# PCB_Telemetria_2020.net
KiCad netlist of a schematic drawn in EAGLE
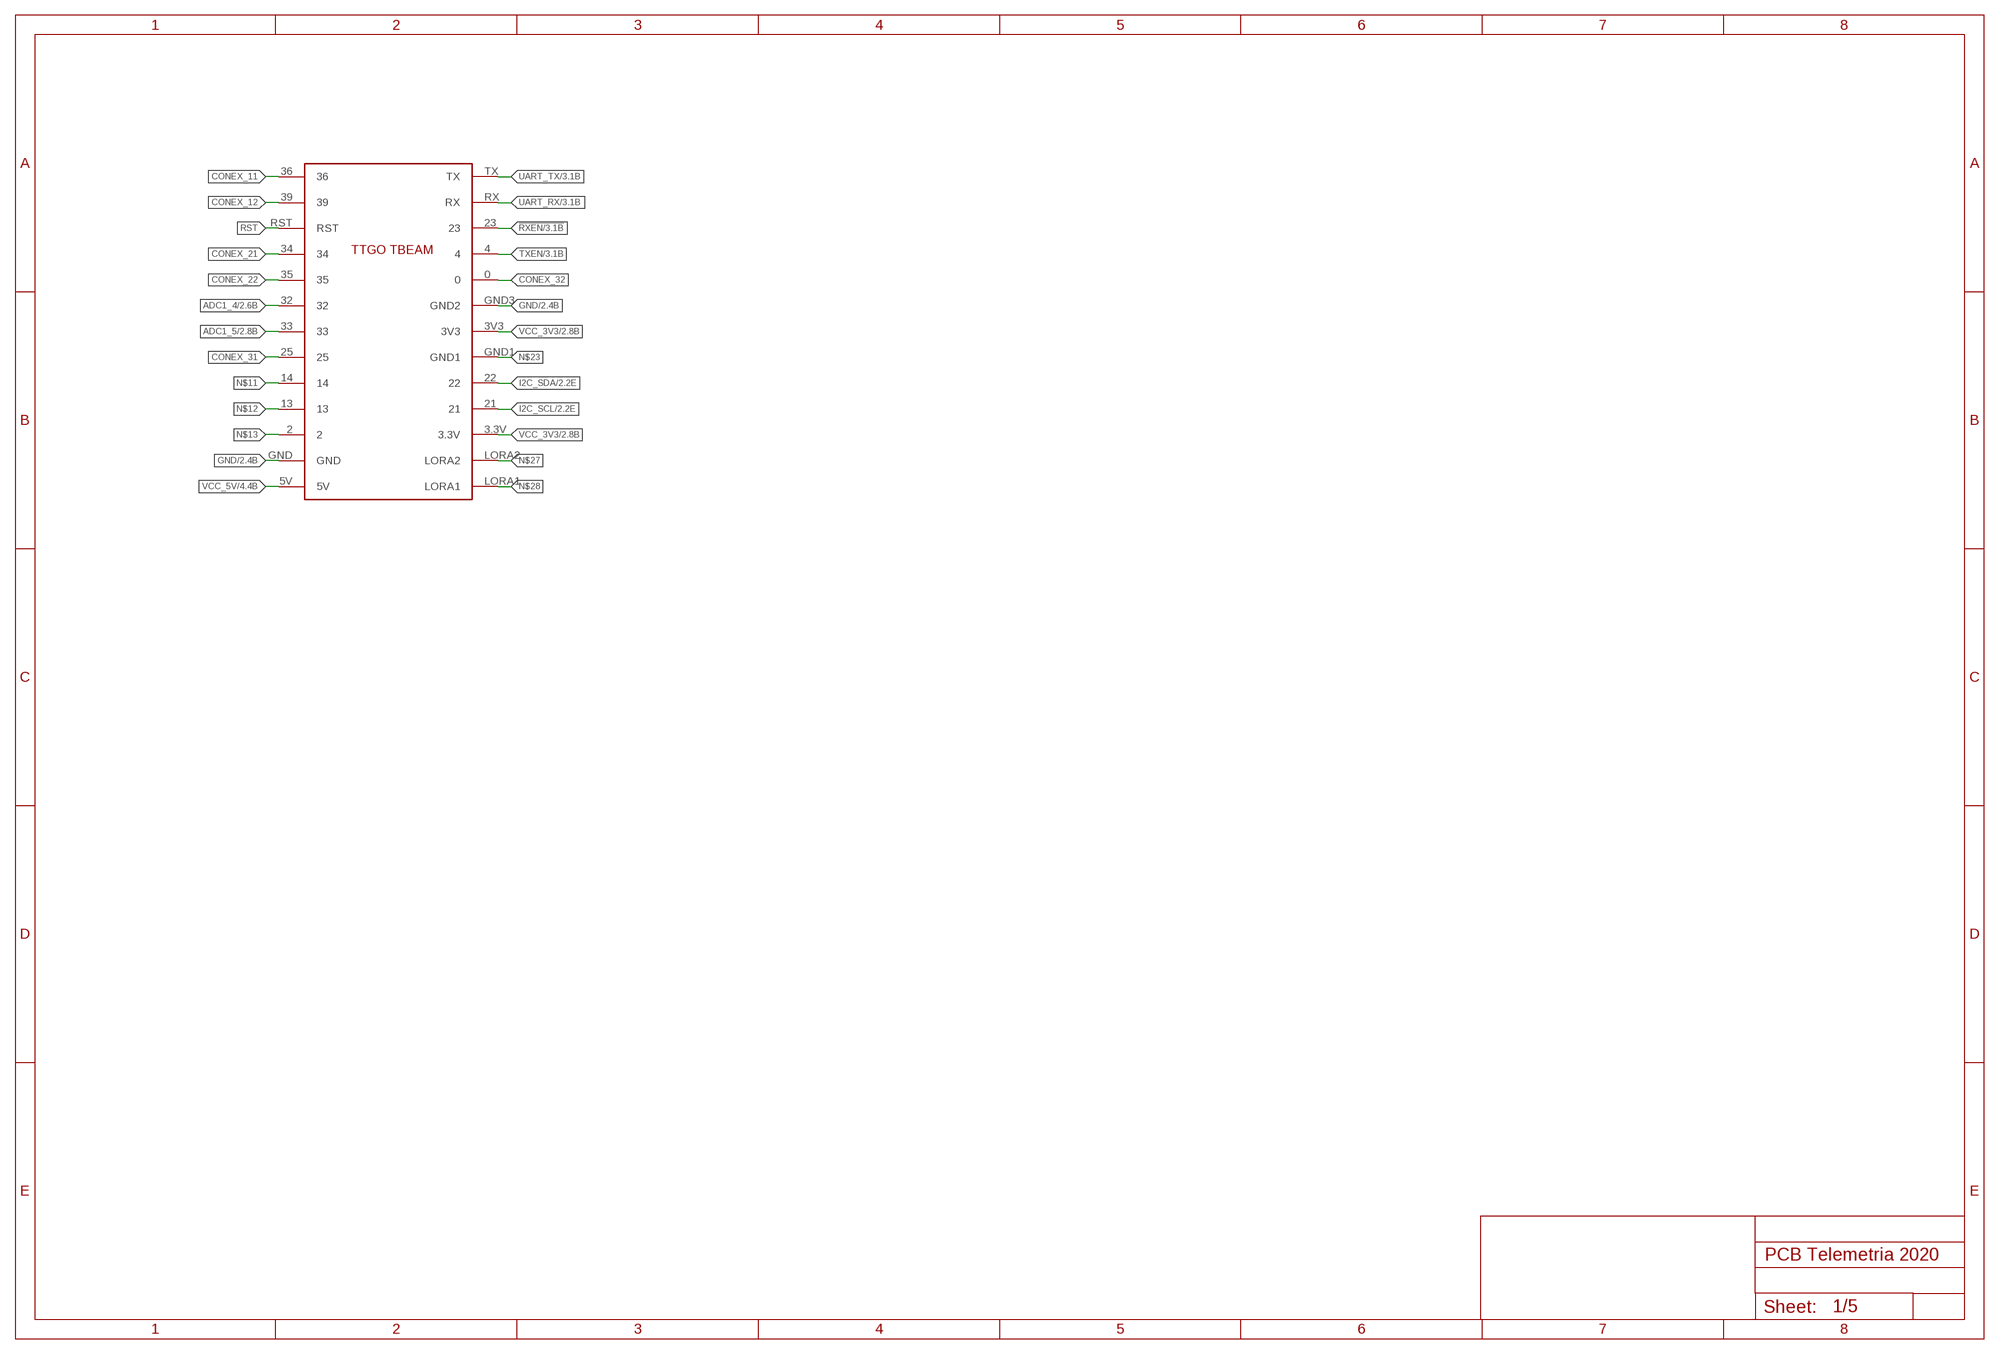
[diagram p0: schematic, sheet 1]
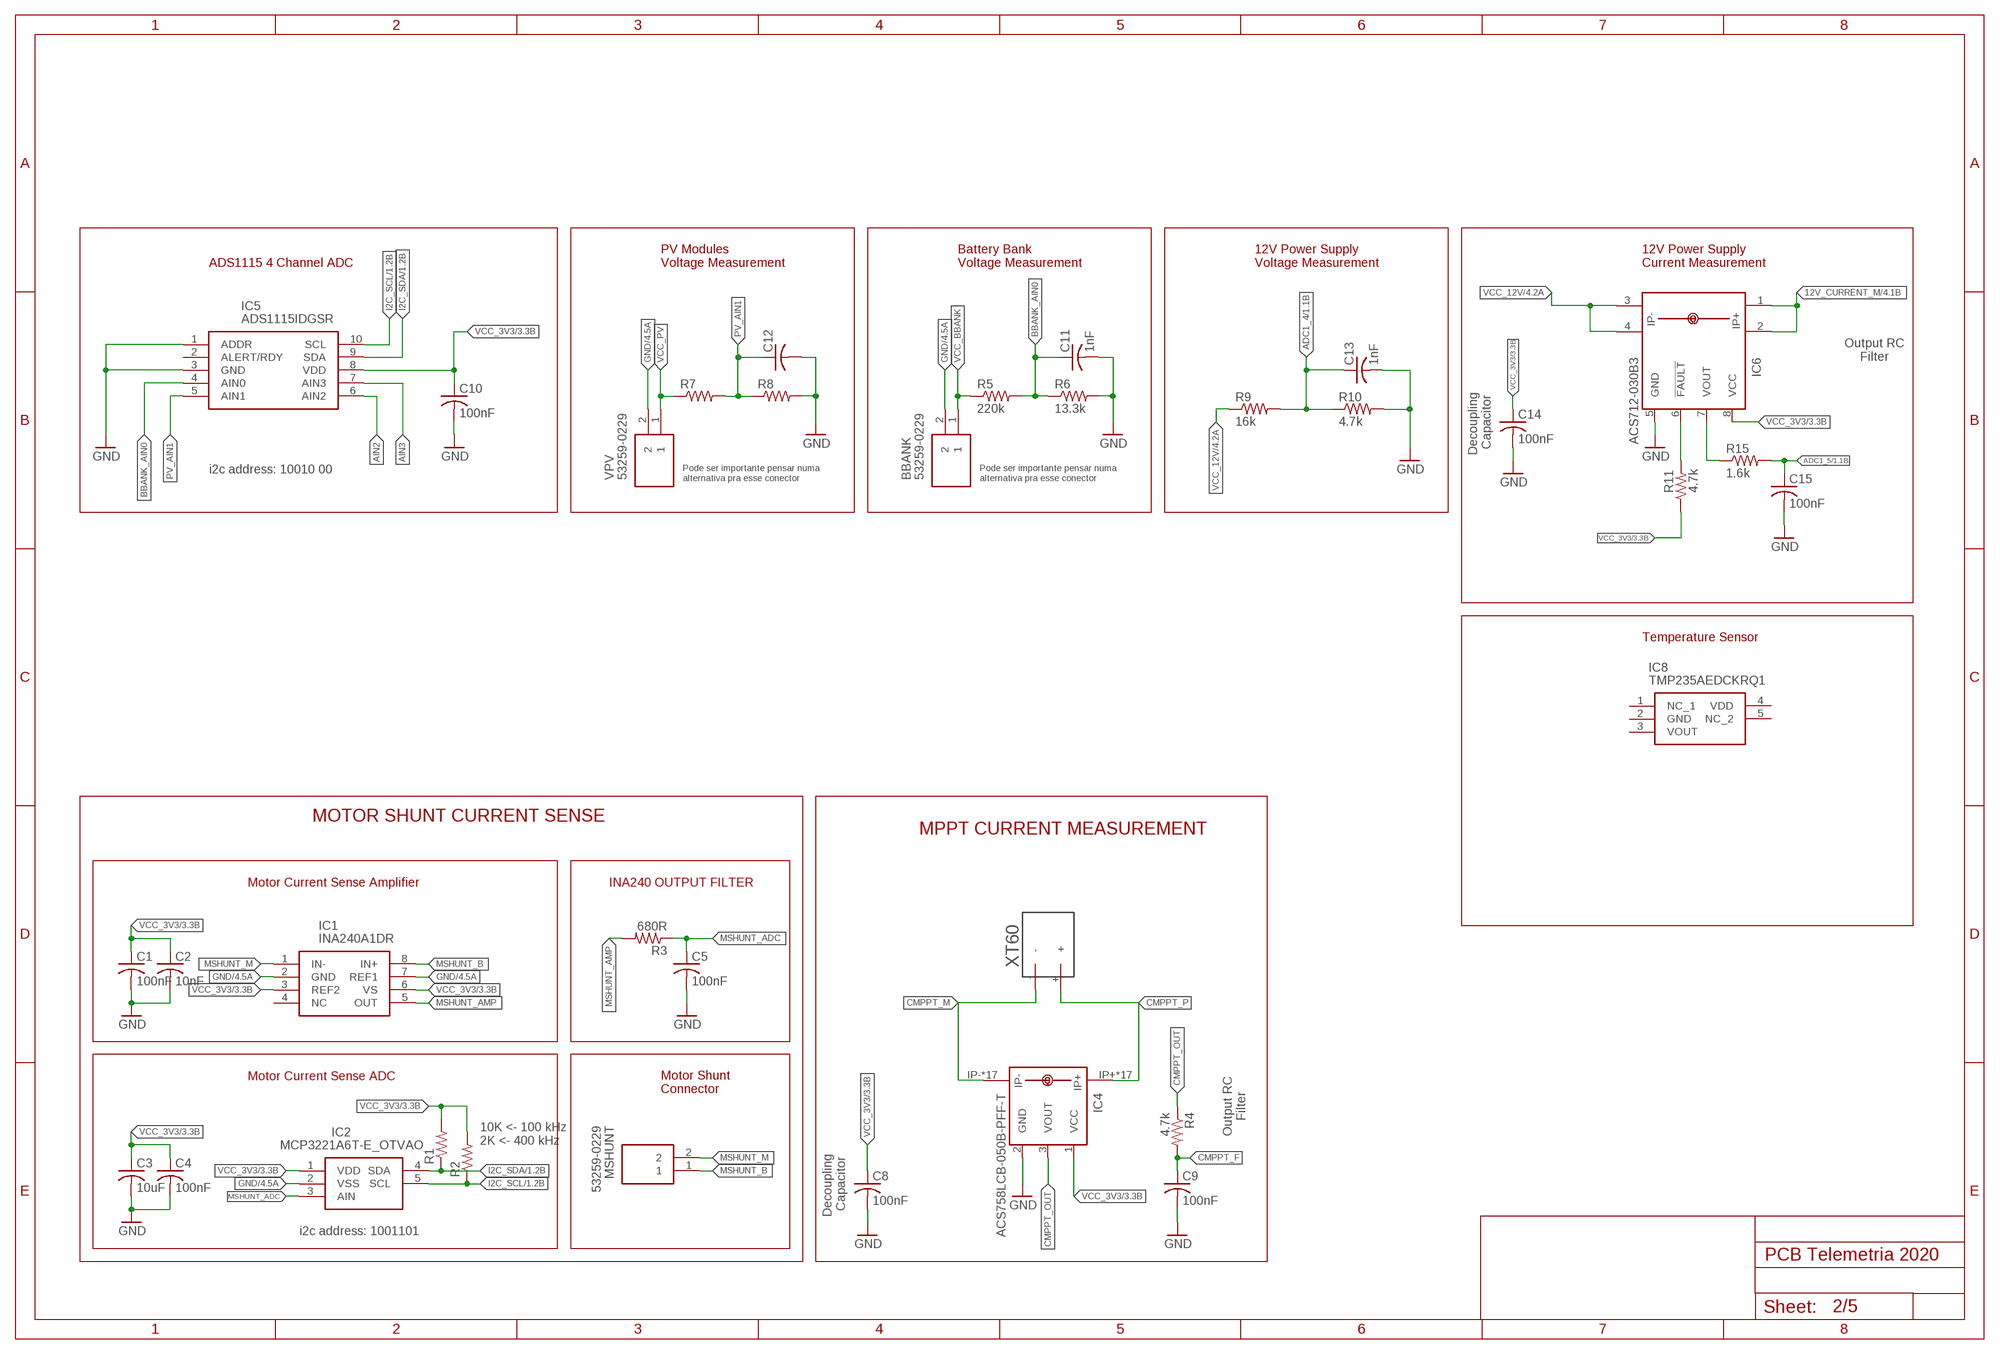
[diagram p1: schematic, sheet 2]
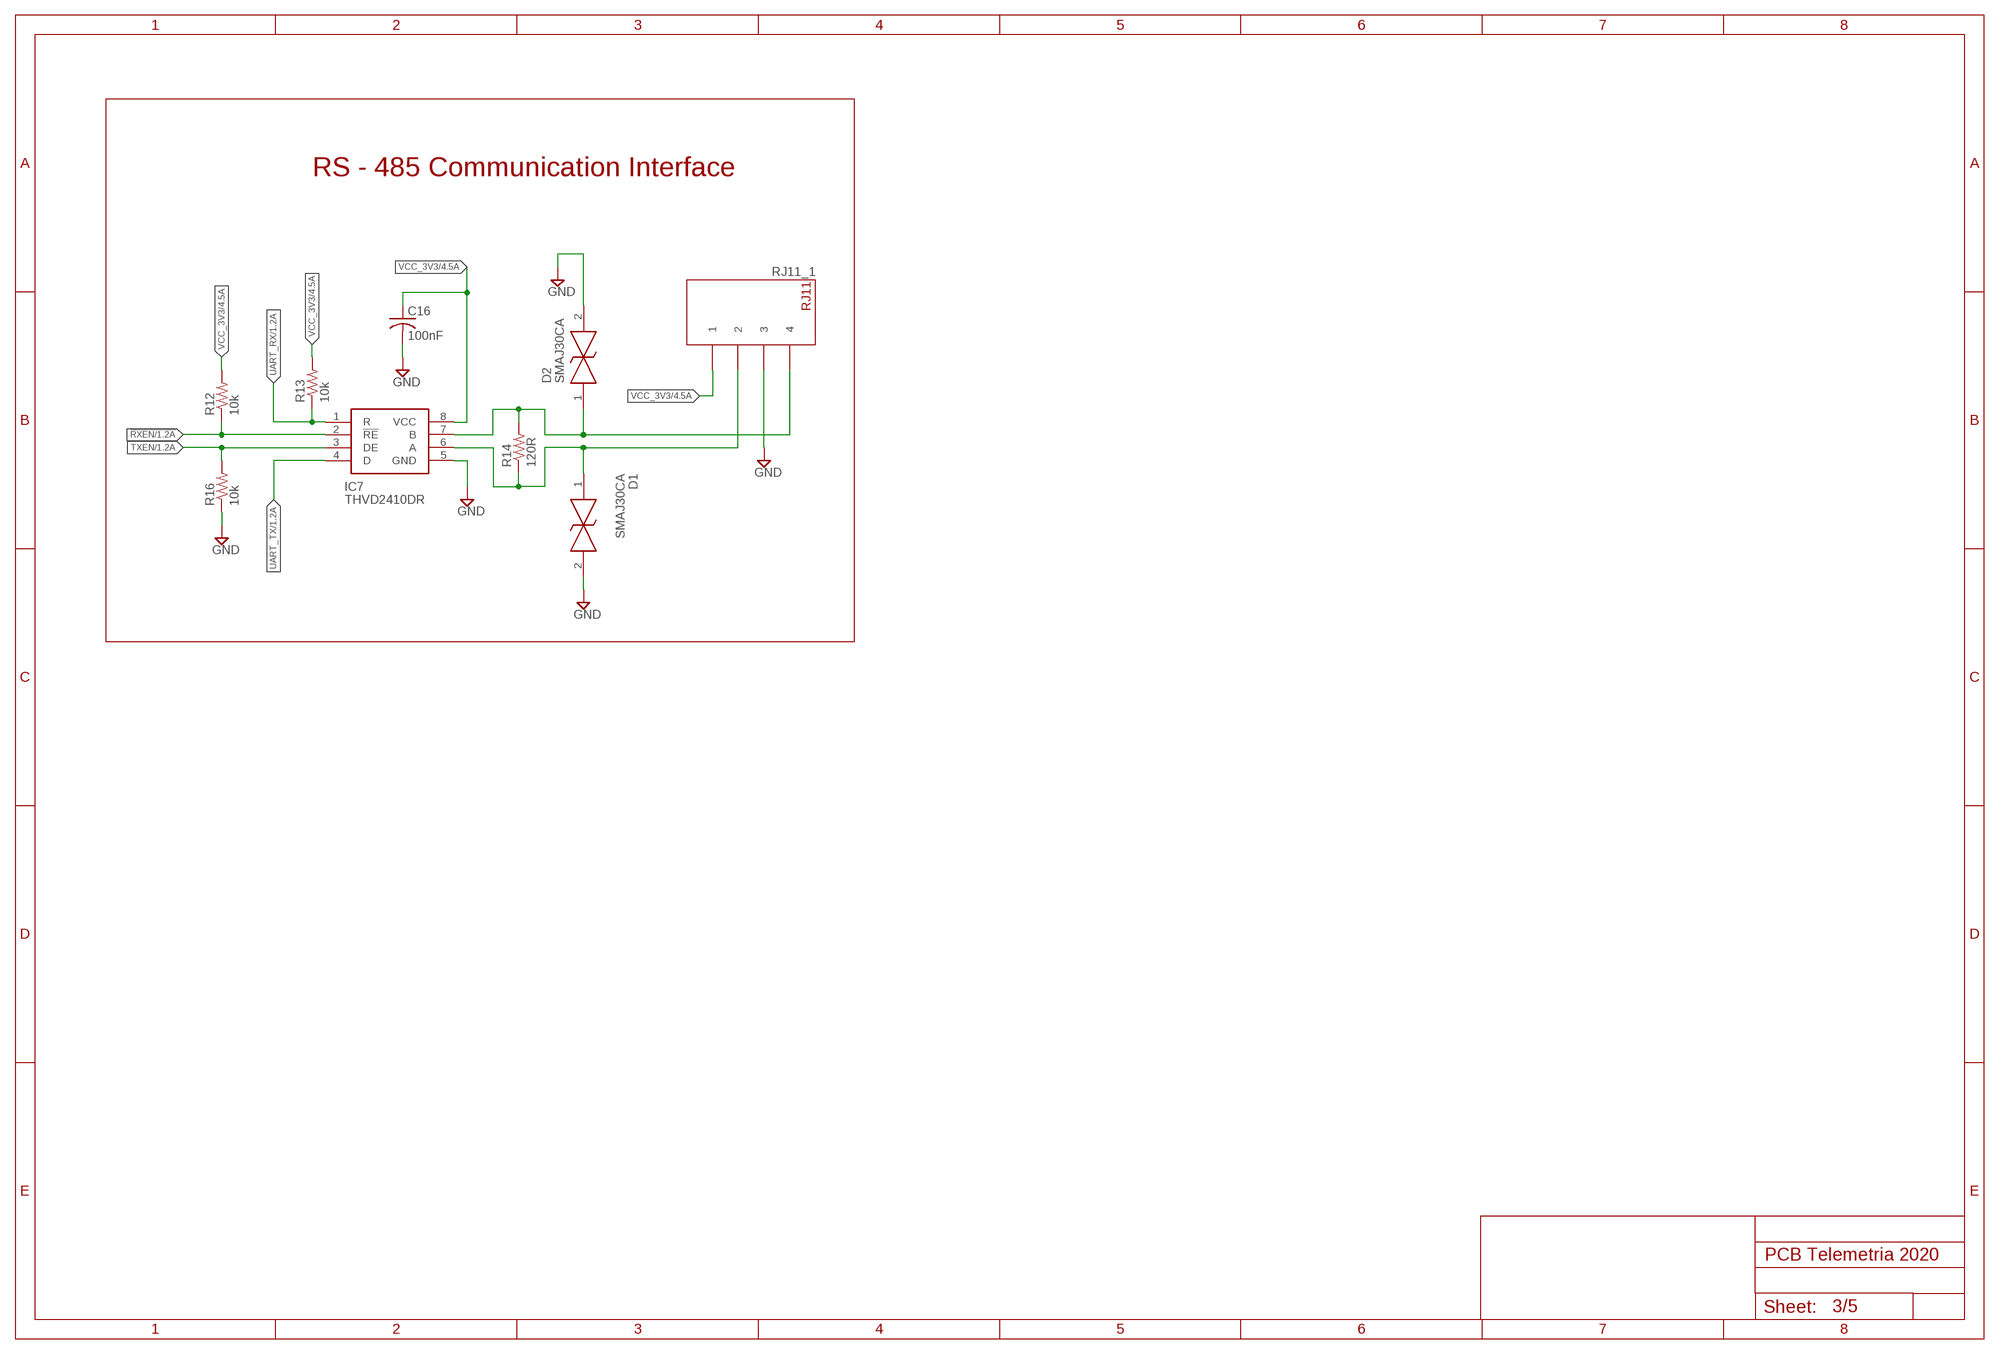
[diagram p2: schematic, sheet 3]
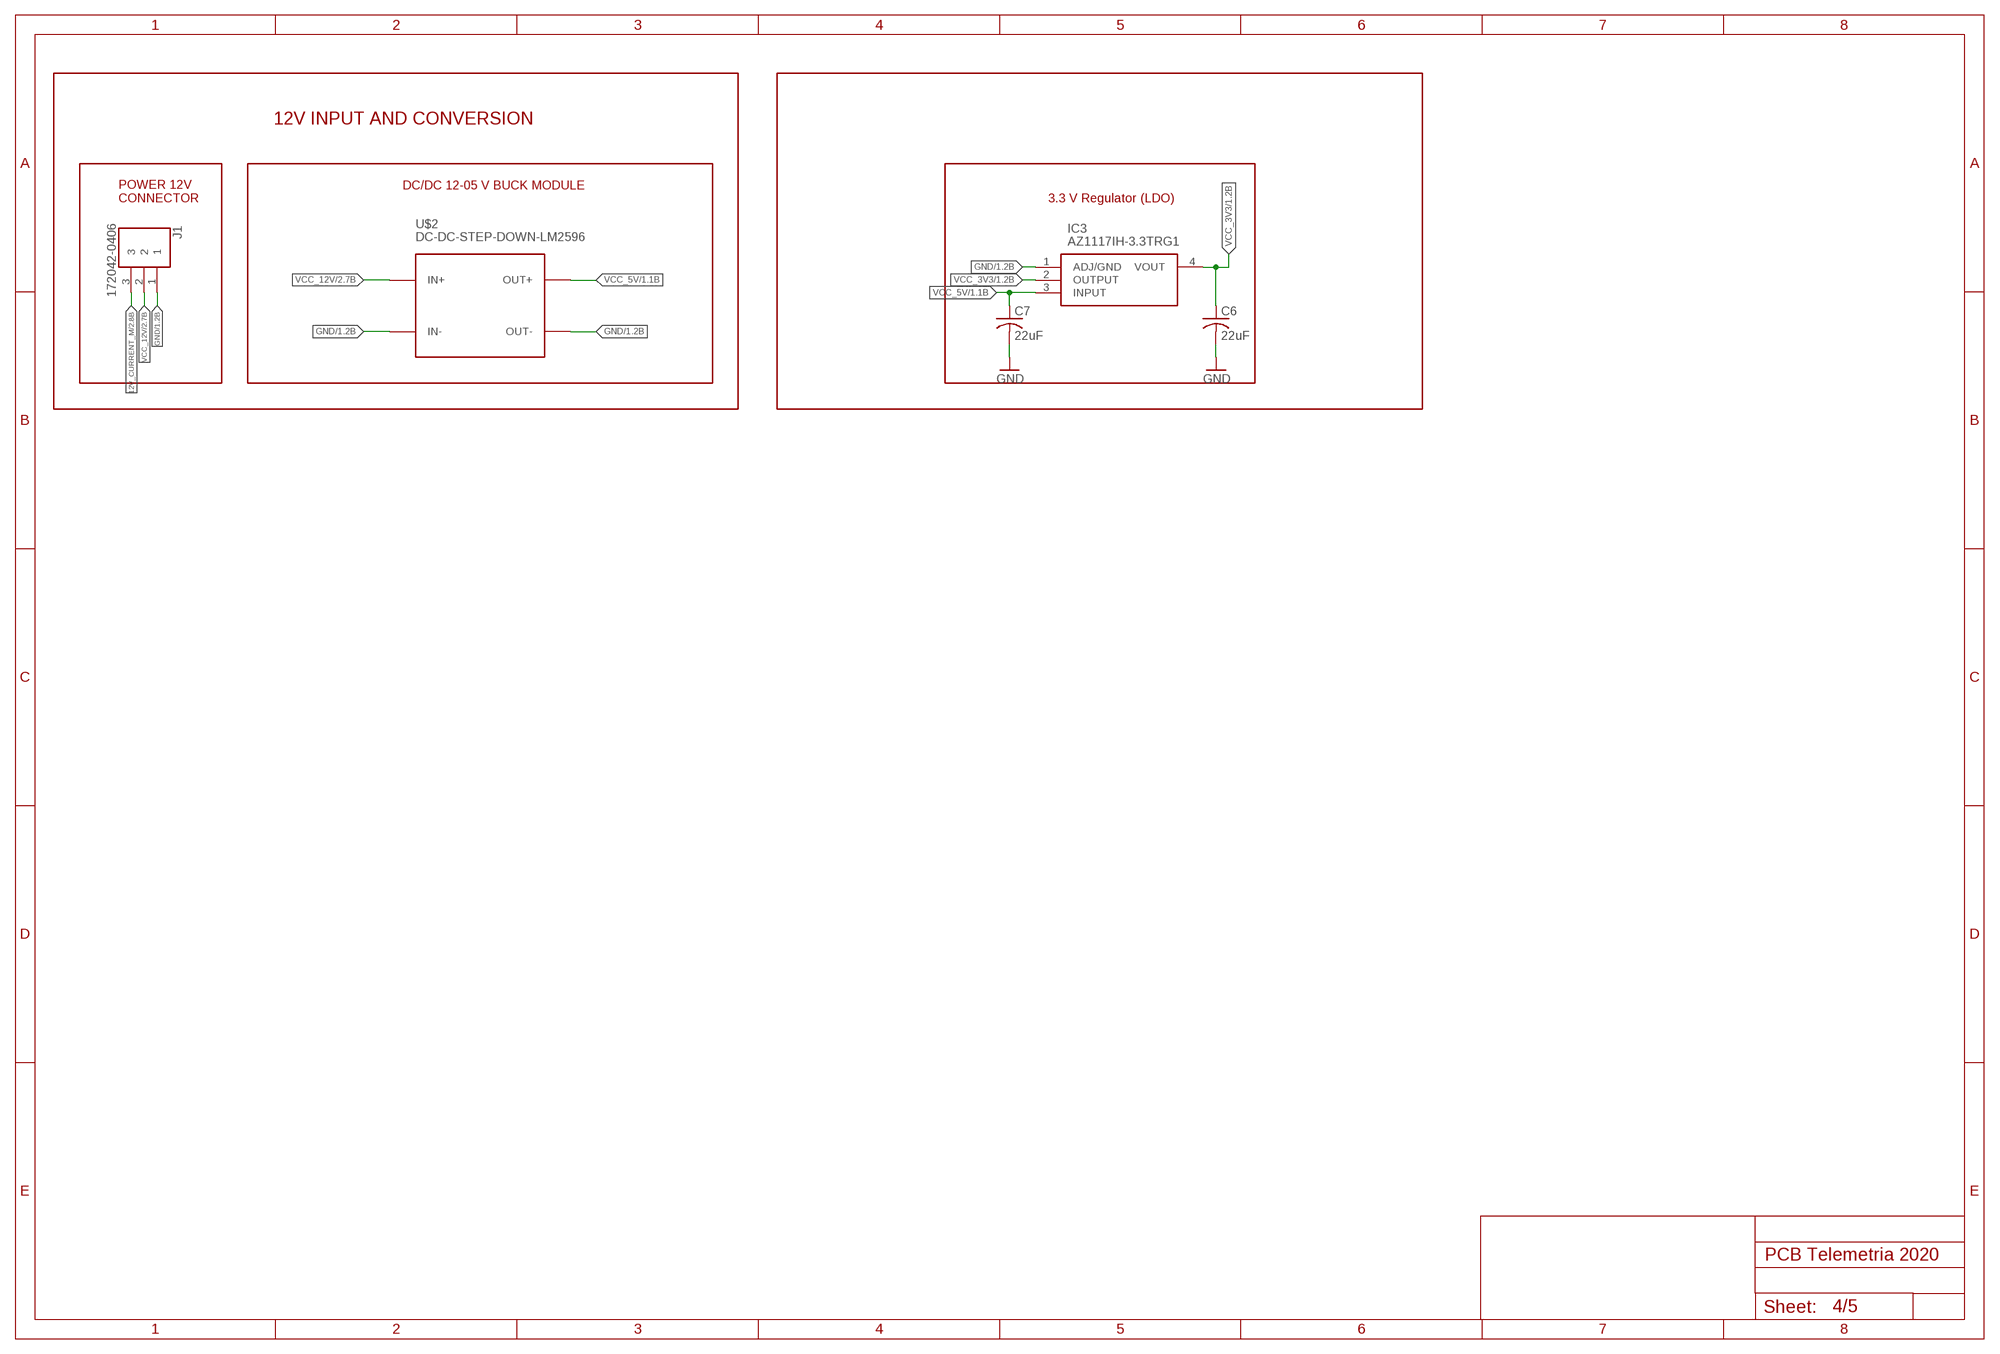
[diagram p3: schematic, sheet 4]
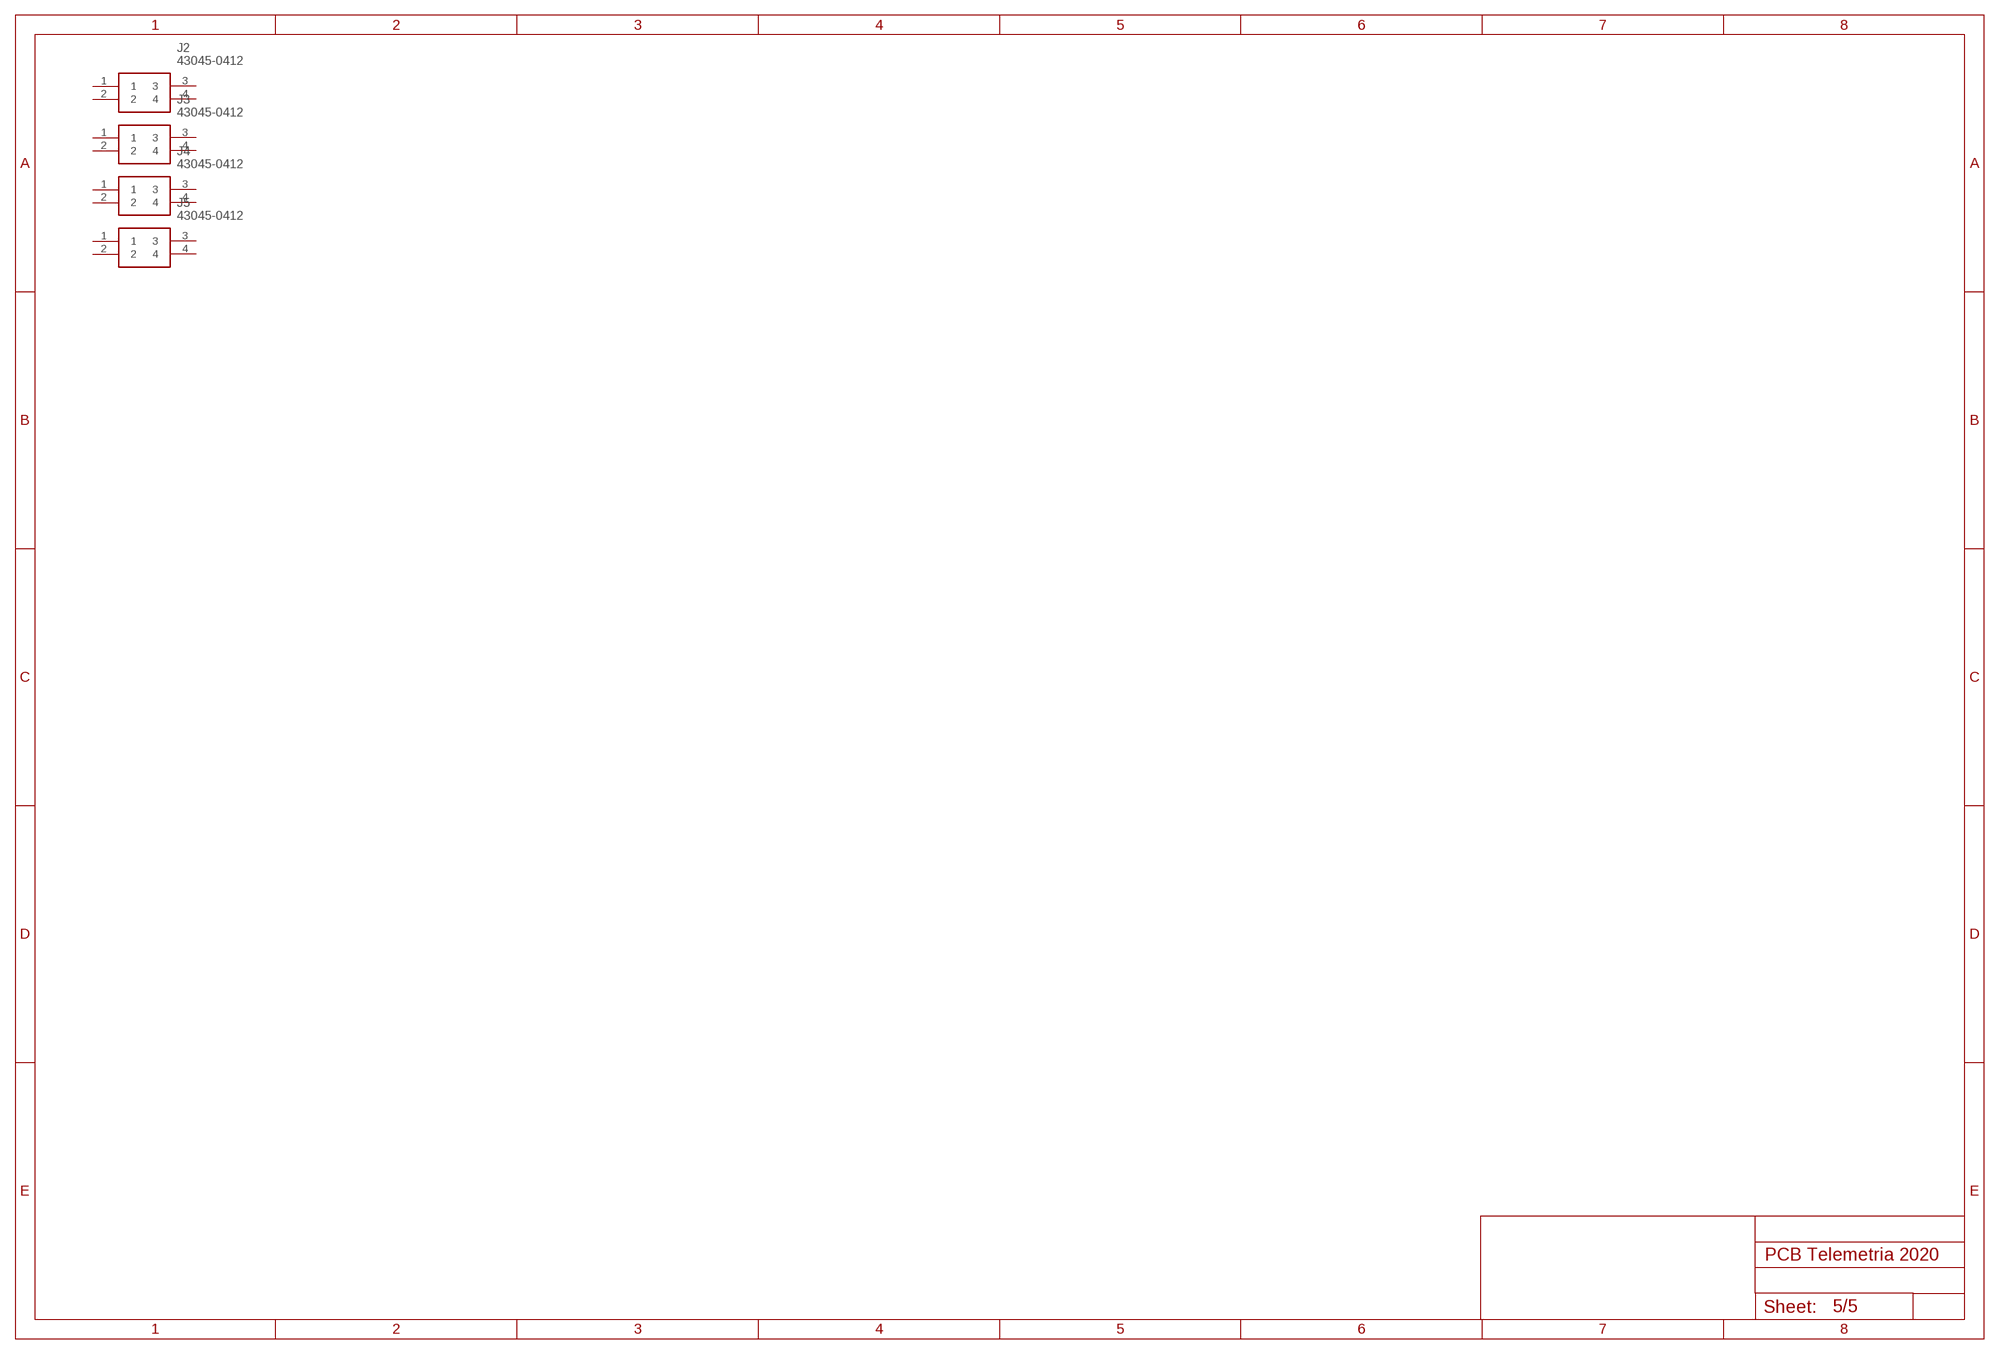
[diagram p4: schematic, sheet 5]

(export (version "E")
  (design (tool "Eeschema 10.0.6"))
  (components
    (comp (ref "U$1")
      (value "TTGOBEAM")
      (footprint "eagle-import:TTGOBEAM")
      (libsource (lib "eagle-import") (part "TTGOBEAM"))
    )
    (comp (ref "J2")
      (value "43045-0412")
      (footprint "eagle-import:43045-0412")
      (fields (field (name "MOUSER_PART_NUMBER") "538-43045-0412"))
      (libsource (lib "eagle-import") (part "43045-0412"))
    )
    (comp (ref "J3")
      (value "43045-0412")
      (footprint "eagle-import:43045-0412")
      (fields (field (name "MOUSER_PART_NUMBER") "538-43045-0412"))
      (libsource (lib "eagle-import") (part "43045-0412"))
    )
    (comp (ref "J4")
      (value "43045-0412")
      (footprint "eagle-import:43045-0412")
      (fields (field (name "MOUSER_PART_NUMBER") "538-43045-0412"))
      (libsource (lib "eagle-import") (part "43045-0412"))
    )
    (comp (ref "J5")
      (value "43045-0412")
      (footprint "eagle-import:43045-0412")
      (fields (field (name "MOUSER_PART_NUMBER") "538-43045-0412"))
      (libsource (lib "eagle-import") (part "43045-0412"))
    )
    (comp (ref "C6")
      (value "22uF")
      (footprint "eagle-import:C0805")
      (libsource (lib "eagle-import") (part "C-USC0805"))
    )
    (comp (ref "C7")
      (value "22uF")
      (footprint "eagle-import:C0805")
      (libsource (lib "eagle-import") (part "C-USC0805"))
    )
    (comp (ref "IC3")
      (value "AZ1117IH-3.3TRG1")
      (footprint "eagle-import:SOT230P700X170-4N")
      (fields (field (name "MOUSER_PART_NUMBER") "621-AZ1117IH-3.3TRG1"))
      (libsource (lib "eagle-import") (part "AZ1117IH-3.3TRG1"))
    )
    (comp (ref "J1")
      (value "172042-0406")
      (footprint "eagle-import:MOLEX_172042-0406")
      (fields (field (name "MF") "Molex") (field (name "MP") "172042-0302"))
      (libsource (lib "eagle-import") (part "172042-0406"))
    )
    (comp (ref "U$2")
      (value "DC-DC-STEP-DOWN-LM2596")
      (footprint "eagle-import:DC-DC-STEP-DOWN-LM2596")
      (libsource (lib "eagle-import") (part "DC-DC-STEP-DOWN-LM2596"))
    )
    (comp (ref "BBANK")
      (value "53259-0229")
      (footprint "eagle-import:0532590229")
      (fields (field (name "MOUSER_PART_NUMBER") "538-53259-0229"))
      (libsource (lib "eagle-import") (part "53259-0229"))
    )
    (comp (ref "C1")
      (value "100nF")
      (footprint "eagle-import:C0805")
      (libsource (lib "eagle-import") (part "C-USC0805"))
    )
    (comp (ref "C2")
      (value "10nF")
      (footprint "eagle-import:C0805")
      (libsource (lib "eagle-import") (part "C-USC0805"))
    )
    (comp (ref "C3")
      (value "10uF")
      (footprint "eagle-import:C0805")
      (libsource (lib "eagle-import") (part "C-USC0805"))
    )
    (comp (ref "C4")
      (value "100nF")
      (footprint "eagle-import:C0805")
      (libsource (lib "eagle-import") (part "C-USC0805"))
    )
    (comp (ref "C5")
      (value "100nF")
      (footprint "eagle-import:C0805")
      (libsource (lib "eagle-import") (part "C-USC0805"))
    )
    (comp (ref "C8")
      (value "100nF")
      (footprint "eagle-import:C0805")
      (libsource (lib "eagle-import") (part "C-USC0805"))
    )
    (comp (ref "C9")
      (value "100nF")
      (footprint "eagle-import:C0805")
      (libsource (lib "eagle-import") (part "C-USC0805"))
    )
    (comp (ref "C10")
      (value "100nF")
      (footprint "eagle-import:C0805")
      (libsource (lib "eagle-import") (part "C-USC0805"))
    )
    (comp (ref "C11")
      (value "1nF")
      (footprint "eagle-import:C0805")
      (libsource (lib "eagle-import") (part "C-USC0805"))
    )
    (comp (ref "C12")
      (value "C-USC0805")
      (footprint "eagle-import:C0805")
      (libsource (lib "eagle-import") (part "C-USC0805"))
    )
    (comp (ref "C13")
      (value "1nF")
      (footprint "eagle-import:C0805")
      (libsource (lib "eagle-import") (part "C-USC0805"))
    )
    (comp (ref "C14")
      (value "100nF")
      (footprint "eagle-import:C0805")
      (libsource (lib "eagle-import") (part "C-USC0805"))
    )
    (comp (ref "C15")
      (value "100nF")
      (footprint "eagle-import:C0805")
      (libsource (lib "eagle-import") (part "C-USC0805"))
    )
    (comp (ref "IC1")
      (value "INA240A1DR")
      (footprint "eagle-import:SOIC127P600X175-8N")
      (fields (field (name "MOUSER_PART_NUMBER") "595-INA240A1DR"))
      (libsource (lib "eagle-import") (part "INA240A1DR"))
    )
    (comp (ref "IC2")
      (value "MCP3221A6T-E_OTVAO")
      (footprint "eagle-import:SOT95P280X145-5N")
      (fields
        (field (name "MANUFACTURER_PART_NUMBER") "MCP3221A6T-E/OTVAO")
        (field (name "MOUSER_PART_NUMBER") "579-MCP3221A6TEOTVAO")
      )
      (libsource (lib "eagle-import") (part "MCP3221A6T-E_OTVAO"))
    )
    (comp (ref "IC4")
      (value "ACS758LCB-050B-PFF-T")
      (footprint "eagle-import:CB-PFF")
      (libsource (lib "eagle-import") (part "ACS758LCB-050B-PFF-T"))
    )
    (comp (ref "IC5")
      (value "ADS1115IDGSR")
      (footprint "eagle-import:SOP50P490X110-10N")
      (fields (field (name "MOUSER_PART_NUMBER") "595-ADS1115IDGSR"))
      (libsource (lib "eagle-import") (part "ADS1115IDGSR"))
    )
    (comp (ref "IC6")
      (value "ACS712-030B3")
      (footprint "eagle-import:SOIC8")
      (libsource (lib "eagle-import") (part "ACS712-LC"))
    )
    (comp (ref "IC8")
      (value "TMP235AEDCKRQ1")
      (footprint "eagle-import:SOT65P210X110-5N")
      (fields (field (name "MOUSER_PART_NUMBER") "595-TMP235AEDCKRQ1"))
      (libsource (lib "eagle-import") (part "TMP235AEDCKRQ1"))
    )
    (comp (ref "MSHUNT")
      (value "53259-0229")
      (footprint "eagle-import:0532590229")
      (fields (field (name "MOUSER_PART_NUMBER") "538-53259-0229"))
      (libsource (lib "eagle-import") (part "53259-0229"))
    )
    (comp (ref "R1")
      (value "R-US_R0805")
      (footprint "eagle-import:R0805")
      (libsource (lib "eagle-import") (part "R-US_R0805"))
    )
    (comp (ref "R2")
      (value "R-US_R0805")
      (footprint "eagle-import:R0805")
      (libsource (lib "eagle-import") (part "R-US_R0805"))
    )
    (comp (ref "R3")
      (value "680R")
      (footprint "eagle-import:R0805")
      (libsource (lib "eagle-import") (part "R-US_R0805"))
    )
    (comp (ref "R4")
      (value "4.7k")
      (footprint "eagle-import:R0805")
      (libsource (lib "eagle-import") (part "R-US_R0805"))
    )
    (comp (ref "R5")
      (value "220k")
      (footprint "eagle-import:R0805")
      (libsource (lib "eagle-import") (part "R-US_R0805"))
    )
    (comp (ref "R6")
      (value "13.3k")
      (footprint "eagle-import:R0805")
      (libsource (lib "eagle-import") (part "R-US_R0805"))
    )
    (comp (ref "R7")
      (value "R-US_R0805")
      (footprint "eagle-import:R0805")
      (libsource (lib "eagle-import") (part "R-US_R0805"))
    )
    (comp (ref "R8")
      (value "R-US_R0805")
      (footprint "eagle-import:R0805")
      (libsource (lib "eagle-import") (part "R-US_R0805"))
    )
    (comp (ref "R9")
      (value "16k")
      (footprint "eagle-import:R0805")
      (libsource (lib "eagle-import") (part "R-US_R0805"))
    )
    (comp (ref "R10")
      (value "4.7k")
      (footprint "eagle-import:R0805")
      (libsource (lib "eagle-import") (part "R-US_R0805"))
    )
    (comp (ref "R11")
      (value "4.7k")
      (footprint "eagle-import:R0805")
      (libsource (lib "eagle-import") (part "R-US_R0805"))
    )
    (comp (ref "R15")
      (value "1.6k")
      (footprint "eagle-import:R0805")
      (libsource (lib "eagle-import") (part "R-US_R0805"))
    )
    (comp (ref "U$3")
      (value "XT60")
      (footprint "eagle-import:XT60")
      (libsource (lib "eagle-import") (part "XT60"))
    )
    (comp (ref "VPV")
      (value "53259-0229")
      (footprint "eagle-import:0532590229")
      (fields (field (name "MOUSER_PART_NUMBER") "538-53259-0229"))
      (libsource (lib "eagle-import") (part "53259-0229"))
    )
    (comp (ref "C16")
      (value "100nF")
      (footprint "eagle-import:C0805")
      (libsource (lib "eagle-import") (part "C-USC0805"))
    )
    (comp (ref "D1")
      (value "SMAJ30CA")
      (footprint "eagle-import:DIONM5026X229N")
      (fields (field (name "MOUSER_PART_NUMBER") "576-SMAJ30CA"))
      (libsource (lib "eagle-import") (part "SMAJ30CA"))
    )
    (comp (ref "D2")
      (value "SMAJ30CA")
      (footprint "eagle-import:DIONM5026X229N")
      (fields (field (name "MOUSER_PART_NUMBER") "576-SMAJ30CA"))
      (libsource (lib "eagle-import") (part "SMAJ30CA"))
    )
    (comp (ref "IC7")
      (value "THVD2410DR")
      (footprint "eagle-import:SOIC127P600X175-8N")
      (fields (field (name "MOUSER_PART_NUMBER") "595-THVD2410DR"))
      (libsource (lib "eagle-import") (part "THVD2410DR"))
    )
    (comp (ref "R12")
      (value "10k")
      (footprint "eagle-import:M0805")
      (libsource (lib "eagle-import") (part "R-US_M0805"))
    )
    (comp (ref "R13")
      (value "10k")
      (footprint "eagle-import:M0805")
      (libsource (lib "eagle-import") (part "R-US_M0805"))
    )
    (comp (ref "R14")
      (value "120R")
      (footprint "eagle-import:M0805")
      (libsource (lib "eagle-import") (part "R-US_M0805"))
    )
    (comp (ref "R16")
      (value "10k")
      (footprint "eagle-import:M0805")
      (libsource (lib "eagle-import") (part "R-US_M0805"))
    )
    (comp (ref "RJ11_1")
      (value "TFC44")
      (footprint "eagle-import:TFC44")
      (libsource (lib "eagle-import") (part "TFC44"))
    )
  )
  (nets
    (net (code "1") (name "12V_CURRENT_M") (class "Default")
      (node (ref "IC6") (pin "1") (pinfunction "IP+_1") (pintype "passive"))
      (node (ref "IC6") (pin "2") (pinfunction "IP+1_2") (pintype "passive"))
      (node (ref "J1") (pin "3") (pinfunction "3_3") (pintype "passive"))
    )
    (net (code "2") (name "ADC1_4") (class "Default")
      (node (ref "C13") (pin "1") (pinfunction "1_1") (pintype "passive"))
      (node (ref "R10") (pin "1") (pinfunction "1_1") (pintype "passive"))
      (node (ref "R9") (pin "2") (pinfunction "2_2") (pintype "passive"))
      (node (ref "U$1") (pin "32") (pinfunction "32_32") (pintype "bidirectional"))
    )
    (net (code "3") (name "ADC1_5") (class "Default")
      (node (ref "C15") (pin "1") (pinfunction "1_1") (pintype "passive"))
      (node (ref "R15") (pin "2") (pinfunction "2_2") (pintype "passive"))
      (node (ref "U$1") (pin "33") (pinfunction "33_33") (pintype "bidirectional"))
    )
    (net (code "4") (name "AIN2") (class "Default")
      (node (ref "IC5") (pin "6") (pinfunction "AIN2_6") (pintype "bidirectional"))
    )
    (net (code "5") (name "AIN3") (class "Default")
      (node (ref "IC5") (pin "7") (pinfunction "AIN3_7") (pintype "bidirectional"))
    )
    (net (code "6") (name "BBANK_AIN0") (class "Default")
      (node (ref "C11") (pin "1") (pinfunction "1_1") (pintype "passive"))
      (node (ref "IC5") (pin "4") (pinfunction "AIN0_4") (pintype "bidirectional"))
      (node (ref "R5") (pin "2") (pinfunction "2_2") (pintype "passive"))
      (node (ref "R6") (pin "1") (pinfunction "1_1") (pintype "passive"))
    )
    (net (code "7") (name "CMPPT_F") (class "Default")
      (node (ref "C9") (pin "1") (pinfunction "1_1") (pintype "passive"))
      (node (ref "R4") (pin "2") (pinfunction "2_2") (pintype "passive"))
    )
    (net (code "8") (name "CMPPT_M") (class "Default")
      (node (ref "IC4") (pin "IP-") (pinfunction "IP-_IP-") (pintype "passive"))
      (node (ref "IC4") (pin "IP-@10") (pinfunction "IP-_IP-@10") (pintype "passive"))
      (node (ref "IC4") (pin "IP-@11") (pinfunction "IP-_IP-@11") (pintype "passive"))
      (node (ref "IC4") (pin "IP-@12") (pinfunction "IP-_IP-@12") (pintype "passive"))
      (node (ref "IC4") (pin "IP-@13") (pinfunction "IP-_IP-@13") (pintype "passive"))
      (node (ref "IC4") (pin "IP-@14") (pinfunction "IP-_IP-@14") (pintype "passive"))
      (node (ref "IC4") (pin "IP-@15") (pinfunction "IP-_IP-@15") (pintype "passive"))
      (node (ref "IC4") (pin "IP-@16") (pinfunction "IP-_IP-@16") (pintype "passive"))
      (node (ref "IC4") (pin "IP-@17") (pinfunction "IP-_IP-@17") (pintype "passive"))
      (node (ref "IC4") (pin "IP-@2") (pinfunction "IP-_IP-@2") (pintype "passive"))
      (node (ref "IC4") (pin "IP-@3") (pinfunction "IP-_IP-@3") (pintype "passive"))
      (node (ref "IC4") (pin "IP-@4") (pinfunction "IP-_IP-@4") (pintype "passive"))
      (node (ref "IC4") (pin "IP-@5") (pinfunction "IP-_IP-@5") (pintype "passive"))
      (node (ref "IC4") (pin "IP-@6") (pinfunction "IP-_IP-@6") (pintype "passive"))
      (node (ref "IC4") (pin "IP-@7") (pinfunction "IP-_IP-@7") (pintype "passive"))
      (node (ref "IC4") (pin "IP-@8") (pinfunction "IP-_IP-@8") (pintype "passive"))
      (node (ref "IC4") (pin "IP-@9") (pinfunction "IP-_IP-@9") (pintype "passive"))
      (node (ref "U$3") (pin "-") (pinfunction "-_-") (pintype "bidirectional"))
    )
    (net (code "9") (name "CMPPT_OUT") (class "Default")
      (node (ref "IC4") (pin "3") (pinfunction "VOUT_3") (pintype "output"))
      (node (ref "R4") (pin "1") (pinfunction "1_1") (pintype "passive"))
    )
    (net (code "10") (name "CMPPT_P") (class "Default")
      (node (ref "IC4") (pin "IP+") (pinfunction "IP+_IP+") (pintype "passive"))
      (node (ref "IC4") (pin "IP+@10") (pinfunction "IP+_IP+@10") (pintype "passive"))
      (node (ref "IC4") (pin "IP+@11") (pinfunction "IP+_IP+@11") (pintype "passive"))
      (node (ref "IC4") (pin "IP+@12") (pinfunction "IP+_IP+@12") (pintype "passive"))
      (node (ref "IC4") (pin "IP+@13") (pinfunction "IP+_IP+@13") (pintype "passive"))
      (node (ref "IC4") (pin "IP+@14") (pinfunction "IP+_IP+@14") (pintype "passive"))
      (node (ref "IC4") (pin "IP+@15") (pinfunction "IP+_IP+@15") (pintype "passive"))
      (node (ref "IC4") (pin "IP+@16") (pinfunction "IP+_IP+@16") (pintype "passive"))
      (node (ref "IC4") (pin "IP+@17") (pinfunction "IP+_IP+@17") (pintype "passive"))
      (node (ref "IC4") (pin "IP+@2") (pinfunction "IP+_IP+@2") (pintype "passive"))
      (node (ref "IC4") (pin "IP+@3") (pinfunction "IP+_IP+@3") (pintype "passive"))
      (node (ref "IC4") (pin "IP+@4") (pinfunction "IP+_IP+@4") (pintype "passive"))
      (node (ref "IC4") (pin "IP+@5") (pinfunction "IP+_IP+@5") (pintype "passive"))
      (node (ref "IC4") (pin "IP+@6") (pinfunction "IP+_IP+@6") (pintype "passive"))
      (node (ref "IC4") (pin "IP+@7") (pinfunction "IP+_IP+@7") (pintype "passive"))
      (node (ref "IC4") (pin "IP+@8") (pinfunction "IP+_IP+@8") (pintype "passive"))
      (node (ref "IC4") (pin "IP+@9") (pinfunction "IP+_IP+@9") (pintype "passive"))
      (node (ref "U$3") (pin "+") (pinfunction "+_+") (pintype "bidirectional"))
    )
    (net (code "11") (name "CONEX_11") (class "Default")
      (node (ref "U$1") (pin "36") (pinfunction "36_36") (pintype "bidirectional"))
    )
    (net (code "12") (name "CONEX_12") (class "Default")
      (node (ref "U$1") (pin "39") (pinfunction "39_39") (pintype "bidirectional"))
    )
    (net (code "13") (name "CONEX_21") (class "Default")
      (node (ref "U$1") (pin "34") (pinfunction "34_34") (pintype "bidirectional"))
    )
    (net (code "14") (name "CONEX_22") (class "Default")
      (node (ref "U$1") (pin "35") (pinfunction "35_35") (pintype "bidirectional"))
    )
    (net (code "15") (name "CONEX_31") (class "Default")
      (node (ref "U$1") (pin "25") (pinfunction "25_25") (pintype "bidirectional"))
    )
    (net (code "16") (name "CONEX_32") (class "Default")
      (node (ref "U$1") (pin "0") (pinfunction "0_0") (pintype "bidirectional"))
    )
    (net (code "17") (name "GND") (class "Default")
      (node (ref "BBANK") (pin "2") (pinfunction "2_2") (pintype "bidirectional"))
      (node (ref "C1") (pin "2") (pinfunction "2_2") (pintype "passive"))
      (node (ref "C10") (pin "2") (pinfunction "2_2") (pintype "passive"))
      (node (ref "C11") (pin "2") (pinfunction "2_2") (pintype "passive"))
      (node (ref "C12") (pin "2") (pinfunction "2_2") (pintype "passive"))
      (node (ref "C13") (pin "2") (pinfunction "2_2") (pintype "passive"))
      (node (ref "C14") (pin "2") (pinfunction "2_2") (pintype "passive"))
      (node (ref "C15") (pin "2") (pinfunction "2_2") (pintype "passive"))
      (node (ref "C16") (pin "2") (pinfunction "2_2") (pintype "passive"))
      (node (ref "C2") (pin "2") (pinfunction "2_2") (pintype "passive"))
      (node (ref "C3") (pin "2") (pinfunction "2_2") (pintype "passive"))
      (node (ref "C4") (pin "2") (pinfunction "2_2") (pintype "passive"))
      (node (ref "C5") (pin "2") (pinfunction "2_2") (pintype "passive"))
      (node (ref "C6") (pin "2") (pinfunction "2_2") (pintype "passive"))
      (node (ref "C7") (pin "2") (pinfunction "2_2") (pintype "passive"))
      (node (ref "C8") (pin "2") (pinfunction "2_2") (pintype "passive"))
      (node (ref "C9") (pin "2") (pinfunction "2_2") (pintype "passive"))
      (node (ref "D1") (pin "2") (pinfunction "2_2") (pintype "bidirectional"))
      (node (ref "D2") (pin "2") (pinfunction "2_2") (pintype "bidirectional"))
      (node (ref "IC1") (pin "2") (pinfunction "GND_2") (pintype "bidirectional"))
      (node (ref "IC1") (pin "7") (pinfunction "REF1_7") (pintype "bidirectional"))
      (node (ref "IC2") (pin "2") (pinfunction "VSS_2") (pintype "bidirectional"))
      (node (ref "IC3") (pin "1") (pinfunction "ADJ/GND_1") (pintype "bidirectional"))
      (node (ref "IC4") (pin "2") (pinfunction "GND_2") (pintype "power_in"))
      (node (ref "IC5") (pin "1") (pinfunction "ADDR_1") (pintype "bidirectional"))
      (node (ref "IC5") (pin "3") (pinfunction "GND_3") (pintype "bidirectional"))
      (node (ref "IC6") (pin "5") (pinfunction "GND_5") (pintype "power_in"))
      (node (ref "IC7") (pin "5") (pinfunction "GND_5") (pintype "bidirectional"))
      (node (ref "J1") (pin "1") (pinfunction "1_1") (pintype "passive"))
      (node (ref "R10") (pin "2") (pinfunction "2_2") (pintype "passive"))
      (node (ref "R16") (pin "1") (pinfunction "1_1") (pintype "passive"))
      (node (ref "R6") (pin "2") (pinfunction "2_2") (pintype "passive"))
      (node (ref "R8") (pin "2") (pinfunction "2_2") (pintype "passive"))
      (node (ref "RJ11_1") (pin "P$3") (pinfunction "3_P$3") (pintype "bidirectional"))
      (node (ref "U$1") (pin "GND") (pinfunction "GND_GND") (pintype "bidirectional"))
      (node (ref "U$1") (pin "GND3") (pinfunction "GND2_GND3") (pintype "bidirectional"))
      (node (ref "U$2") (pin "IN-") (pinfunction "IN-_IN-") (pintype "bidirectional"))
      (node (ref "U$2") (pin "OUT-") (pinfunction "OUT-_OUT-") (pintype "bidirectional"))
      (node (ref "VPV") (pin "2") (pinfunction "2_2") (pintype "bidirectional"))
    )
    (net (code "18") (name "I2C_SCL") (class "Default")
      (node (ref "IC2") (pin "5") (pinfunction "SCL_5") (pintype "bidirectional"))
      (node (ref "IC5") (pin "10") (pinfunction "SCL_10") (pintype "bidirectional"))
      (node (ref "R2") (pin "1") (pinfunction "1_1") (pintype "passive"))
      (node (ref "U$1") (pin "21") (pinfunction "21_21") (pintype "bidirectional"))
    )
    (net (code "19") (name "I2C_SDA") (class "Default")
      (node (ref "IC2") (pin "4") (pinfunction "SDA_4") (pintype "bidirectional"))
      (node (ref "IC5") (pin "9") (pinfunction "SDA_9") (pintype "bidirectional"))
      (node (ref "R1") (pin "1") (pinfunction "1_1") (pintype "passive"))
      (node (ref "U$1") (pin "22") (pinfunction "22_22") (pintype "bidirectional"))
    )
    (net (code "20") (name "MSHUNT_ADC") (class "Default")
      (node (ref "C5") (pin "1") (pinfunction "1_1") (pintype "passive"))
      (node (ref "IC2") (pin "3") (pinfunction "AIN_3") (pintype "bidirectional"))
      (node (ref "R3") (pin "1") (pinfunction "1_1") (pintype "passive"))
    )
    (net (code "21") (name "MSHUNT_AMP") (class "Default")
      (node (ref "IC1") (pin "5") (pinfunction "OUT_5") (pintype "bidirectional"))
      (node (ref "R3") (pin "2") (pinfunction "2_2") (pintype "passive"))
    )
    (net (code "22") (name "MSHUNT_B") (class "Default")
      (node (ref "IC1") (pin "8") (pinfunction "IN+_8") (pintype "bidirectional"))
      (node (ref "MSHUNT") (pin "1") (pinfunction "1_1") (pintype "bidirectional"))
    )
    (net (code "23") (name "MSHUNT_M") (class "Default")
      (node (ref "IC1") (pin "1") (pinfunction "IN-_1") (pintype "bidirectional"))
      (node (ref "MSHUNT") (pin "2") (pinfunction "2_2") (pintype "bidirectional"))
    )
    (net (code "24") (name "N$11") (class "Default")
      (node (ref "U$1") (pin "14") (pinfunction "14_14") (pintype "bidirectional"))
    )
    (net (code "25") (name "N$12") (class "Default")
      (node (ref "U$1") (pin "13") (pinfunction "13_13") (pintype "bidirectional"))
    )
    (net (code "26") (name "N$13") (class "Default")
      (node (ref "U$1") (pin "2") (pinfunction "2_2") (pintype "bidirectional"))
    )
    (net (code "27") (name "N$23") (class "Default")
      (node (ref "U$1") (pin "GND1") (pinfunction "GND1_GND1") (pintype "bidirectional"))
    )
    (net (code "28") (name "N$27") (class "Default")
      (node (ref "U$1") (pin "LORA2") (pinfunction "LORA2_LORA2") (pintype "bidirectional"))
    )
    (net (code "29") (name "N$28") (class "Default")
      (node (ref "U$1") (pin "LORA1") (pinfunction "LORA1_LORA1") (pintype "bidirectional"))
    )
    (net (code "30") (name "Net-(IC6-VOUT)") (class "Default")
      (node (ref "IC6") (pin "7") (pinfunction "VOUT_7") (pintype "output"))
      (node (ref "R15") (pin "1") (pinfunction "1_1") (pintype "passive"))
    )
    (net (code "31") (name "Net-(IC6-~{FAULT})") (class "Default")
      (node (ref "IC6") (pin "6") (pinfunction "~{FAULT}_6") (pintype "bidirectional"))
      (node (ref "R11") (pin "2") (pinfunction "2_2") (pintype "passive"))
    )
    (net (code "32") (name "Net-(IC7-A)") (class "Default")
      (node (ref "D1") (pin "1") (pinfunction "1_1") (pintype "bidirectional"))
      (node (ref "IC7") (pin "6") (pinfunction "A_6") (pintype "bidirectional"))
      (node (ref "R14") (pin "1") (pinfunction "1_1") (pintype "passive"))
      (node (ref "RJ11_1") (pin "P$2") (pinfunction "2_P$2") (pintype "bidirectional"))
    )
    (net (code "33") (name "Net-(IC7-B)") (class "Default")
      (node (ref "D2") (pin "1") (pinfunction "1_1") (pintype "bidirectional"))
      (node (ref "IC7") (pin "7") (pinfunction "B_7") (pintype "bidirectional"))
      (node (ref "R14") (pin "2") (pinfunction "2_2") (pintype "passive"))
      (node (ref "RJ11_1") (pin "P$4") (pinfunction "4_P$4") (pintype "bidirectional"))
    )
    (net (code "34") (name "PV_AIN1") (class "Default")
      (node (ref "C12") (pin "1") (pinfunction "1_1") (pintype "passive"))
      (node (ref "IC5") (pin "5") (pinfunction "AIN1_5") (pintype "bidirectional"))
      (node (ref "R7") (pin "2") (pinfunction "2_2") (pintype "passive"))
      (node (ref "R8") (pin "1") (pinfunction "1_1") (pintype "passive"))
    )
    (net (code "35") (name "RST") (class "Default")
      (node (ref "U$1") (pin "RST") (pinfunction "RST_RST") (pintype "bidirectional"))
    )
    (net (code "36") (name "TXEN") (class "Default")
      (node (ref "IC7") (pin "3") (pinfunction "DE_3") (pintype "bidirectional"))
      (node (ref "R16") (pin "2") (pinfunction "2_2") (pintype "passive"))
      (node (ref "U$1") (pin "4") (pinfunction "4_4") (pintype "bidirectional"))
    )
    (net (code "37") (name "UART_RX") (class "Default")
      (node (ref "IC7") (pin "1") (pinfunction "R_1") (pintype "bidirectional"))
      (node (ref "R13") (pin "1") (pinfunction "1_1") (pintype "passive"))
      (node (ref "U$1") (pin "RX") (pinfunction "RX_RX") (pintype "bidirectional"))
    )
    (net (code "38") (name "UART_TX") (class "Default")
      (node (ref "IC7") (pin "4") (pinfunction "D_4") (pintype "bidirectional"))
      (node (ref "U$1") (pin "TX") (pinfunction "TX_TX") (pintype "bidirectional"))
    )
    (net (code "39") (name "VCC_3V3") (class "Default")
      (node (ref "C1") (pin "1") (pinfunction "1_1") (pintype "passive"))
      (node (ref "C10") (pin "1") (pinfunction "1_1") (pintype "passive"))
      (node (ref "C14") (pin "1") (pinfunction "1_1") (pintype "passive"))
      (node (ref "C16") (pin "1") (pinfunction "1_1") (pintype "passive"))
      (node (ref "C2") (pin "1") (pinfunction "1_1") (pintype "passive"))
      (node (ref "C3") (pin "1") (pinfunction "1_1") (pintype "passive"))
      (node (ref "C4") (pin "1") (pinfunction "1_1") (pintype "passive"))
      (node (ref "C6") (pin "1") (pinfunction "1_1") (pintype "passive"))
      (node (ref "C8") (pin "1") (pinfunction "1_1") (pintype "passive"))
      (node (ref "IC1") (pin "3") (pinfunction "REF2_3") (pintype "bidirectional"))
      (node (ref "IC1") (pin "6") (pinfunction "VS_6") (pintype "bidirectional"))
      (node (ref "IC2") (pin "1") (pinfunction "VDD_1") (pintype "bidirectional"))
      (node (ref "IC3") (pin "2") (pinfunction "OUTPUT_2") (pintype "bidirectional"))
      (node (ref "IC3") (pin "4") (pinfunction "VOUT_4") (pintype "bidirectional"))
      (node (ref "IC4") (pin "1") (pinfunction "VCC_1") (pintype "power_in"))
      (node (ref "IC5") (pin "8") (pinfunction "VDD_8") (pintype "bidirectional"))
      (node (ref "IC6") (pin "8") (pinfunction "VCC_8") (pintype "power_in"))
      (node (ref "IC7") (pin "8") (pinfunction "VCC_8") (pintype "bidirectional"))
      (node (ref "R1") (pin "2") (pinfunction "2_2") (pintype "passive"))
      (node (ref "R11") (pin "1") (pinfunction "1_1") (pintype "passive"))
      (node (ref "R12") (pin "2") (pinfunction "2_2") (pintype "passive"))
      (node (ref "R13") (pin "2") (pinfunction "2_2") (pintype "passive"))
      (node (ref "R2") (pin "2") (pinfunction "2_2") (pintype "passive"))
      (node (ref "RJ11_1") (pin "P$1") (pinfunction "1_P$1") (pintype "bidirectional"))
      (node (ref "U$1") (pin "3.3V") (pinfunction "3.3V_3.3V") (pintype "bidirectional"))
      (node (ref "U$1") (pin "3V3") (pinfunction "3V3_3V3") (pintype "bidirectional"))
    )
    (net (code "40") (name "VCC_5V") (class "Default")
      (node (ref "C7") (pin "1") (pinfunction "1_1") (pintype "passive"))
      (node (ref "IC3") (pin "3") (pinfunction "INPUT_3") (pintype "bidirectional"))
      (node (ref "U$1") (pin "5V") (pinfunction "5V_5V") (pintype "bidirectional"))
      (node (ref "U$2") (pin "OUT+") (pinfunction "OUT+_OUT+") (pintype "bidirectional"))
    )
    (net (code "41") (name "VCC_12V") (class "Default")
      (node (ref "IC6") (pin "3") (pinfunction "IP-_3") (pintype "passive"))
      (node (ref "IC6") (pin "4") (pinfunction "IP-1_4") (pintype "passive"))
      (node (ref "J1") (pin "2") (pinfunction "2_2") (pintype "passive"))
      (node (ref "R9") (pin "1") (pinfunction "1_1") (pintype "passive"))
      (node (ref "U$2") (pin "IN+") (pinfunction "IN+_IN+") (pintype "bidirectional"))
    )
    (net (code "42") (name "VCC_BBANK") (class "Default")
      (node (ref "BBANK") (pin "1") (pinfunction "1_1") (pintype "bidirectional"))
      (node (ref "R5") (pin "1") (pinfunction "1_1") (pintype "passive"))
    )
    (net (code "43") (name "VCC_PV") (class "Default")
      (node (ref "R7") (pin "1") (pinfunction "1_1") (pintype "passive"))
      (node (ref "VPV") (pin "1") (pinfunction "1_1") (pintype "bidirectional"))
    )
    (net (code "44") (name "unconnected-(IC1-NC-Pad4)") (class "Default")
      (node (ref "IC1") (pin "4") (pinfunction "NC_4") (pintype "no_connect"))
    )
    (net (code "45") (name "unconnected-(IC5-ALERT{slash}RDY-Pad2)") (class "Default")
      (node (ref "IC5") (pin "2") (pinfunction "ALERT/RDY_2") (pintype "bidirectional"))
    )
    (net (code "46") (name "unconnected-(IC8-GND-Pad2)") (class "Default")
      (node (ref "IC8") (pin "2") (pinfunction "GND_2") (pintype "bidirectional"))
    )
    (net (code "47") (name "unconnected-(IC8-NC_1-Pad1)") (class "Default")
      (node (ref "IC8") (pin "1") (pinfunction "NC_1_1") (pintype "bidirectional"))
    )
    (net (code "48") (name "unconnected-(IC8-NC_2-Pad5)") (class "Default")
      (node (ref "IC8") (pin "5") (pinfunction "NC_2_5") (pintype "bidirectional"))
    )
    (net (code "49") (name "unconnected-(IC8-VDD-Pad4)") (class "Default")
      (node (ref "IC8") (pin "4") (pinfunction "VDD_4") (pintype "bidirectional"))
    )
    (net (code "50") (name "unconnected-(IC8-VOUT-Pad3)") (class "Default")
      (node (ref "IC8") (pin "3") (pinfunction "VOUT_3") (pintype "bidirectional"))
    )
    (net (code "51") (name "unconnected-(J2-Pad1)") (class "Default")
      (node (ref "J2") (pin "1") (pinfunction "1_1") (pintype "bidirectional"))
    )
    (net (code "52") (name "unconnected-(J2-Pad2)") (class "Default")
      (node (ref "J2") (pin "2") (pinfunction "2_2") (pintype "bidirectional"))
    )
    (net (code "53") (name "unconnected-(J2-Pad3)") (class "Default")
      (node (ref "J2") (pin "3") (pinfunction "3_3") (pintype "bidirectional"))
    )
    (net (code "54") (name "unconnected-(J2-Pad4)") (class "Default")
      (node (ref "J2") (pin "4") (pinfunction "4_4") (pintype "bidirectional"))
    )
    (net (code "55") (name "unconnected-(J3-Pad1)") (class "Default")
      (node (ref "J3") (pin "1") (pinfunction "1_1") (pintype "bidirectional"))
    )
    (net (code "56") (name "unconnected-(J3-Pad2)") (class "Default")
      (node (ref "J3") (pin "2") (pinfunction "2_2") (pintype "bidirectional"))
    )
    (net (code "57") (name "unconnected-(J3-Pad3)") (class "Default")
      (node (ref "J3") (pin "3") (pinfunction "3_3") (pintype "bidirectional"))
    )
    (net (code "58") (name "unconnected-(J3-Pad4)") (class "Default")
      (node (ref "J3") (pin "4") (pinfunction "4_4") (pintype "bidirectional"))
    )
    (net (code "59") (name "unconnected-(J4-Pad1)") (class "Default")
      (node (ref "J4") (pin "1") (pinfunction "1_1") (pintype "bidirectional"))
    )
    (net (code "60") (name "unconnected-(J4-Pad2)") (class "Default")
      (node (ref "J4") (pin "2") (pinfunction "2_2") (pintype "bidirectional"))
    )
    (net (code "61") (name "unconnected-(J4-Pad3)") (class "Default")
      (node (ref "J4") (pin "3") (pinfunction "3_3") (pintype "bidirectional"))
    )
    (net (code "62") (name "unconnected-(J4-Pad4)") (class "Default")
      (node (ref "J4") (pin "4") (pinfunction "4_4") (pintype "bidirectional"))
    )
    (net (code "63") (name "unconnected-(J5-Pad1)") (class "Default")
      (node (ref "J5") (pin "1") (pinfunction "1_1") (pintype "bidirectional"))
    )
    (net (code "64") (name "unconnected-(J5-Pad2)") (class "Default")
      (node (ref "J5") (pin "2") (pinfunction "2_2") (pintype "bidirectional"))
    )
    (net (code "65") (name "unconnected-(J5-Pad3)") (class "Default")
      (node (ref "J5") (pin "3") (pinfunction "3_3") (pintype "bidirectional"))
    )
    (net (code "66") (name "unconnected-(J5-Pad4)") (class "Default")
      (node (ref "J5") (pin "4") (pinfunction "4_4") (pintype "bidirectional"))
    )
    (net (code "67") (name "~{RXEN}") (class "Default")
      (node (ref "IC7") (pin "2") (pinfunction "~{RE}_2") (pintype "bidirectional"))
      (node (ref "R12") (pin "1") (pinfunction "1_1") (pintype "passive"))
      (node (ref "U$1") (pin "23") (pinfunction "23_23") (pintype "bidirectional"))
    )
  )
)
